# Placa_Final_Embebidos_Hoja2.net
KiCad netlist of a schematic drawn in Altium Designer
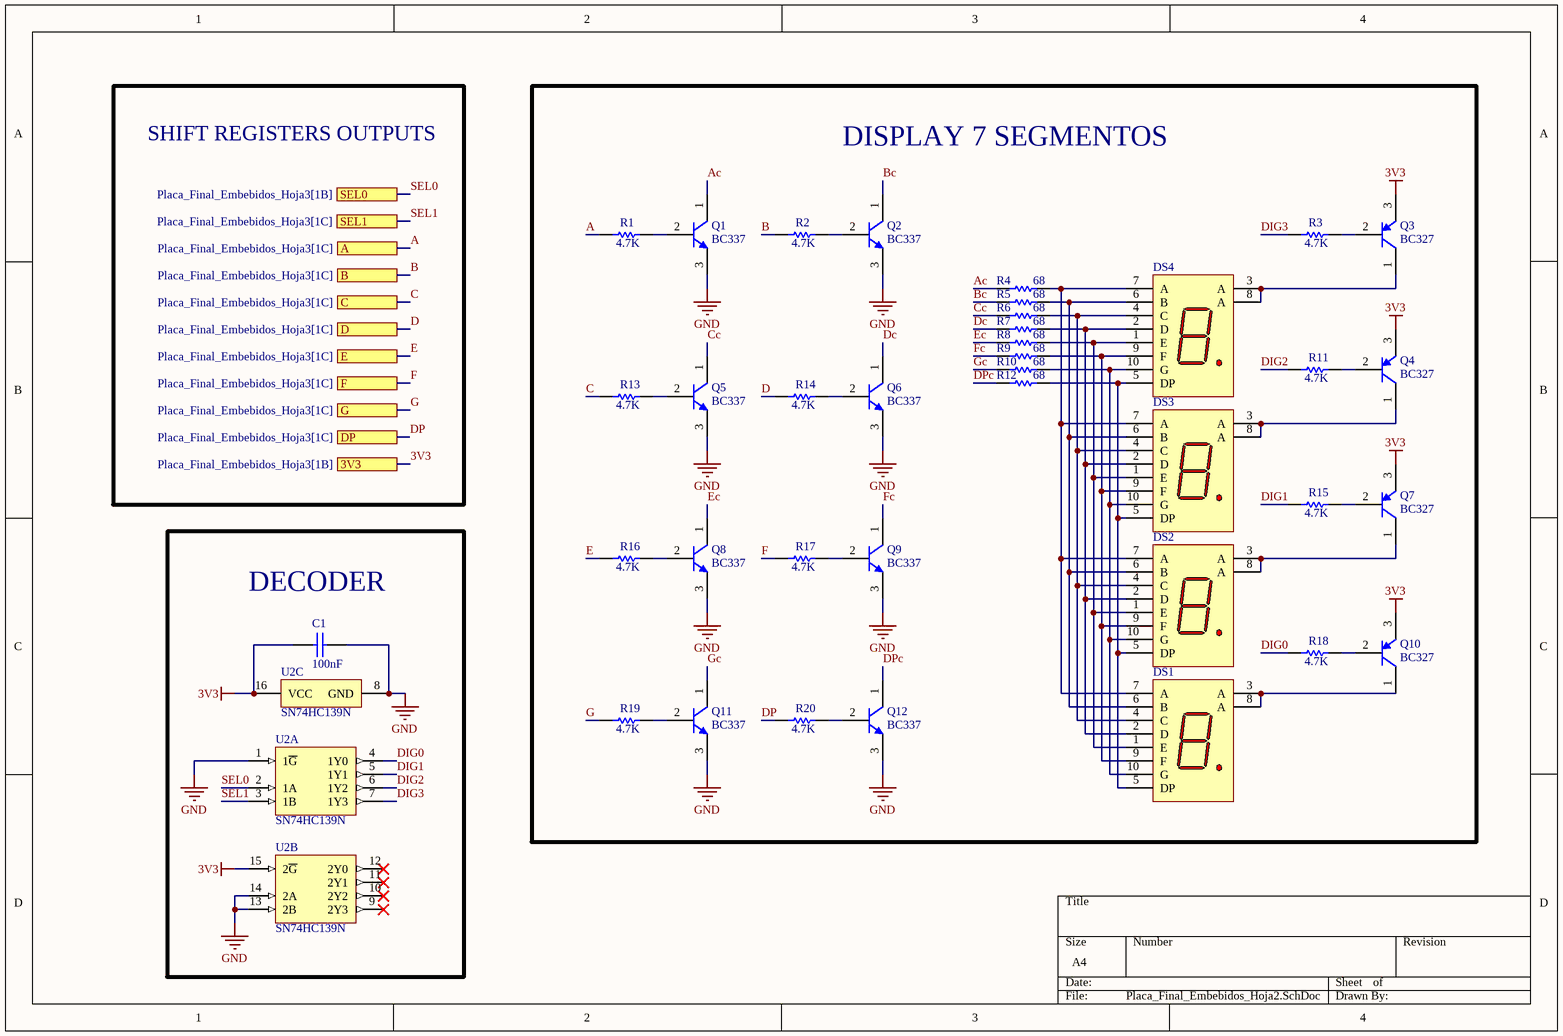
[diagram p0: Placa_Final_Embebidos_Hoja2.SchDoc]

(export (version "E")
  (design (tool "Eeschema 10.0.6"))
  (components
    (comp (ref "C1") (value "100nF") (footprint "CAP200") (libsource (lib "LIB PIO IX") (part "CAP")))
    (comp (ref "DS1")
      (value "~")
      (footprint "WL-T7DS_L17.5W12.4H7")
      (description "7-Seg Display, Comm Anode, Super Red Rohs Compliant: Yes")
      (libsource (lib "Altium Content Vault") (part "7 Segments_Red_CA_type 1"))
    )
    (comp (ref "DS2")
      (value "~")
      (footprint "WL-T7DS_L17.5W12.4H7")
      (description "7-Seg Display, Comm Anode, Super Red Rohs Compliant: Yes")
      (libsource (lib "Altium Content Vault") (part "7 Segments_Red_CA_type 1"))
    )
    (comp (ref "DS3")
      (value "~")
      (footprint "WL-T7DS_L17.5W12.4H7")
      (description "7-Seg Display, Comm Anode, Super Red Rohs Compliant: Yes")
      (libsource (lib "Altium Content Vault") (part "7 Segments_Red_CA_type 1"))
    )
    (comp (ref "DS4")
      (value "~")
      (footprint "WL-T7DS_L17.5W12.4H7")
      (description "7-Seg Display, Comm Anode, Super Red Rohs Compliant: Yes")
      (libsource (lib "Altium Content Vault") (part "7 Segments_Red_CA_type 1"))
    )
    (comp (ref "Q1")
      (value "BC337")
      (footprint "ONSC-TO-92-3-29-11_AM_BL")
      (description "Amplifier Transistor, NPN Silicon, 3-Pin TO-92, Pb-Free, Ammo Box")
      (fields (field (name "PARTNUMBER") "BC337-40ZL1G") (field (name "MANUFACTURER") "On Semiconductor"))
      (libsource (lib "Altium Content Vault") (part "ONSC-NPN-C1B2E3-3"))
    )
    (comp (ref "Q2")
      (value "BC337")
      (footprint "ONSC-TO-92-3-29-11_AM_BL")
      (description "Amplifier Transistor, NPN Silicon, 3-Pin TO-92, Pb-Free, Ammo Box")
      (fields (field (name "PARTNUMBER") "BC337-40ZL1G") (field (name "MANUFACTURER") "On Semiconductor"))
      (libsource (lib "Altium Content Vault") (part "ONSC-NPN-C1B2E3-3"))
    )
    (comp (ref "Q3")
      (value "BC327")
      (footprint "ONSC-TO-92-3-29-11_AM_BL")
      (description "Amplifier Transistor, PNP Silicon, 3-Pin TO-92, Pb-Free, Ammo Box")
      (fields (field (name "MANUFACTURER") "On Semiconductor") (field (name "PARTNUMBER") "BC327-25ZL1G"))
      (libsource (lib "Altium Content Vault") (part "ONSC-PNP-C1B2E3-3"))
    )
    (comp (ref "Q4")
      (value "BC327")
      (footprint "ONSC-TO-92-3-29-11_AM_BL")
      (description "Amplifier Transistor, PNP Silicon, 3-Pin TO-92, Pb-Free, Ammo Box")
      (fields (field (name "MANUFACTURER") "On Semiconductor") (field (name "PARTNUMBER") "BC327-25ZL1G"))
      (libsource (lib "Altium Content Vault") (part "ONSC-PNP-C1B2E3-3"))
    )
    (comp (ref "Q5")
      (value "BC337")
      (footprint "ONSC-TO-92-3-29-11_AM_BL")
      (description "Amplifier Transistor, NPN Silicon, 3-Pin TO-92, Pb-Free, Ammo Box")
      (fields (field (name "PARTNUMBER") "BC337-40ZL1G") (field (name "MANUFACTURER") "On Semiconductor"))
      (libsource (lib "Altium Content Vault") (part "ONSC-NPN-C1B2E3-3"))
    )
    (comp (ref "Q6")
      (value "BC337")
      (footprint "ONSC-TO-92-3-29-11_AM_BL")
      (description "Amplifier Transistor, NPN Silicon, 3-Pin TO-92, Pb-Free, Ammo Box")
      (fields (field (name "PARTNUMBER") "BC337-40ZL1G") (field (name "MANUFACTURER") "On Semiconductor"))
      (libsource (lib "Altium Content Vault") (part "ONSC-NPN-C1B2E3-3"))
    )
    (comp (ref "Q7")
      (value "BC327")
      (footprint "ONSC-TO-92-3-29-11_AM_BL")
      (description "Amplifier Transistor, PNP Silicon, 3-Pin TO-92, Pb-Free, Ammo Box")
      (fields (field (name "MANUFACTURER") "On Semiconductor") (field (name "PARTNUMBER") "BC327-25ZL1G"))
      (libsource (lib "Altium Content Vault") (part "ONSC-PNP-C1B2E3-3"))
    )
    (comp (ref "Q8")
      (value "BC337")
      (footprint "ONSC-TO-92-3-29-11_AM_BL")
      (description "Amplifier Transistor, NPN Silicon, 3-Pin TO-92, Pb-Free, Ammo Box")
      (fields (field (name "PARTNUMBER") "BC337-40ZL1G") (field (name "MANUFACTURER") "On Semiconductor"))
      (libsource (lib "Altium Content Vault") (part "ONSC-NPN-C1B2E3-3"))
    )
    (comp (ref "Q9")
      (value "BC337")
      (footprint "ONSC-TO-92-3-29-11_AM_BL")
      (description "Amplifier Transistor, NPN Silicon, 3-Pin TO-92, Pb-Free, Ammo Box")
      (fields (field (name "PARTNUMBER") "BC337-40ZL1G") (field (name "MANUFACTURER") "On Semiconductor"))
      (libsource (lib "Altium Content Vault") (part "ONSC-NPN-C1B2E3-3"))
    )
    (comp (ref "Q10")
      (value "BC327")
      (footprint "ONSC-TO-92-3-29-11_AM_BL")
      (description "Amplifier Transistor, PNP Silicon, 3-Pin TO-92, Pb-Free, Ammo Box")
      (fields (field (name "MANUFACTURER") "On Semiconductor") (field (name "PARTNUMBER") "BC327-25ZL1G"))
      (libsource (lib "Altium Content Vault") (part "ONSC-PNP-C1B2E3-3"))
    )
    (comp (ref "Q11")
      (value "BC337")
      (footprint "ONSC-TO-92-3-29-11_AM_BL")
      (description "Amplifier Transistor, NPN Silicon, 3-Pin TO-92, Pb-Free, Ammo Box")
      (fields (field (name "PARTNUMBER") "BC337-40ZL1G") (field (name "MANUFACTURER") "On Semiconductor"))
      (libsource (lib "Altium Content Vault") (part "ONSC-NPN-C1B2E3-3"))
    )
    (comp (ref "Q12")
      (value "BC337")
      (footprint "ONSC-TO-92-3-29-11_AM_BL")
      (description "Amplifier Transistor, NPN Silicon, 3-Pin TO-92, Pb-Free, Ammo Box")
      (fields (field (name "PARTNUMBER") "BC337-40ZL1G") (field (name "MANUFACTURER") "On Semiconductor"))
      (libsource (lib "Altium Content Vault") (part "ONSC-NPN-C1B2E3-3"))
    )
    (comp (ref "R1") (value "4.7K") (footprint "RES400") (libsource (lib "LIB PIO IX") (part "RES")))
    (comp (ref "R2") (value "4.7K") (footprint "RES400") (libsource (lib "LIB PIO IX") (part "RES")))
    (comp (ref "R3") (value "4.7K") (footprint "RES400") (libsource (lib "LIB PIO IX") (part "RES")))
    (comp (ref "R4") (value "68") (footprint "RES400") (libsource (lib "LIB PIO IX") (part "RES")))
    (comp (ref "R5") (value "68") (footprint "RES400") (libsource (lib "LIB PIO IX") (part "RES")))
    (comp (ref "R6") (value "68") (footprint "RES400") (libsource (lib "LIB PIO IX") (part "RES")))
    (comp (ref "R7") (value "68") (footprint "RES400") (libsource (lib "LIB PIO IX") (part "RES")))
    (comp (ref "R8") (value "68") (footprint "RES400") (libsource (lib "LIB PIO IX") (part "RES")))
    (comp (ref "R9") (value "68") (footprint "RES400") (libsource (lib "LIB PIO IX") (part "RES")))
    (comp (ref "R10") (value "68") (footprint "RES400") (libsource (lib "LIB PIO IX") (part "RES")))
    (comp (ref "R11") (value "4.7K") (footprint "RES400") (libsource (lib "LIB PIO IX") (part "RES")))
    (comp (ref "R12") (value "68") (footprint "RES400") (libsource (lib "LIB PIO IX") (part "RES")))
    (comp (ref "R13") (value "4.7K") (footprint "RES400") (libsource (lib "LIB PIO IX") (part "RES")))
    (comp (ref "R14") (value "4.7K") (footprint "RES400") (libsource (lib "LIB PIO IX") (part "RES")))
    (comp (ref "R15") (value "4.7K") (footprint "RES400") (libsource (lib "LIB PIO IX") (part "RES")))
    (comp (ref "R16") (value "4.7K") (footprint "RES400") (libsource (lib "LIB PIO IX") (part "RES")))
    (comp (ref "R17") (value "4.7K") (footprint "RES400") (libsource (lib "LIB PIO IX") (part "RES")))
    (comp (ref "R18") (value "4.7K") (footprint "RES400") (libsource (lib "LIB PIO IX") (part "RES")))
    (comp (ref "R19") (value "4.7K") (footprint "RES400") (libsource (lib "LIB PIO IX") (part "RES")))
    (comp (ref "R20") (value "4.7K") (footprint "RES400") (libsource (lib "LIB PIO IX") (part "RES")))
    (comp (ref "U2")
      (value "SN74HC139N")
      (footprint "N0016A")
      (description "Dual 2-Line To 4-Line Decoders/Demultiplexers, N0016A, TUBE")
      (fields
        (field (name "GENERIC PART NUMBER") "SN74HC139")
        (field (name "MANUFACTURER") "Texas Instruments")
      )
      (libsource (lib "Altium Content Vault") (part "TI-CD_SNX4XXX139-16"))
    )
  )
  (nets
    (net (code "1") (name "/A") (class "Default")
      (node (ref "R1") (pin "1") (pinfunction "1_1") (pintype "passive"))
    )
    (net (code "2") (name "/Ac") (class "Default")
      (node (ref "Q1") (pin "1") (pinfunction "C_1") (pintype "passive"))
      (node (ref "R4") (pin "1") (pinfunction "1_1") (pintype "passive"))
    )
    (net (code "3") (name "/B") (class "Default")
      (node (ref "R2") (pin "1") (pinfunction "1_1") (pintype "passive"))
    )
    (net (code "4") (name "/Bc") (class "Default")
      (node (ref "Q2") (pin "1") (pinfunction "C_1") (pintype "passive"))
      (node (ref "R5") (pin "1") (pinfunction "1_1") (pintype "passive"))
    )
    (net (code "5") (name "/C") (class "Default")
      (node (ref "R13") (pin "1") (pinfunction "1_1") (pintype "passive"))
    )
    (net (code "6") (name "/Cc") (class "Default")
      (node (ref "Q5") (pin "1") (pinfunction "C_1") (pintype "passive"))
      (node (ref "R6") (pin "1") (pinfunction "1_1") (pintype "passive"))
    )
    (net (code "7") (name "/D") (class "Default")
      (node (ref "R14") (pin "1") (pinfunction "1_1") (pintype "passive"))
    )
    (net (code "8") (name "/DIG0") (class "Default")
      (node (ref "R18") (pin "1") (pinfunction "1_1") (pintype "passive"))
      (node (ref "U2") (pin "4") (pinfunction "1Y0_4") (pintype "output"))
    )
    (net (code "9") (name "/DIG1") (class "Default")
      (node (ref "R15") (pin "1") (pinfunction "1_1") (pintype "passive"))
      (node (ref "U2") (pin "5") (pinfunction "1Y1_5") (pintype "output"))
    )
    (net (code "10") (name "/DIG2") (class "Default")
      (node (ref "R11") (pin "1") (pinfunction "1_1") (pintype "passive"))
      (node (ref "U2") (pin "6") (pinfunction "1Y2_6") (pintype "output"))
    )
    (net (code "11") (name "/DIG3") (class "Default")
      (node (ref "R3") (pin "1") (pinfunction "1_1") (pintype "passive"))
      (node (ref "U2") (pin "7") (pinfunction "1Y3_7") (pintype "output"))
    )
    (net (code "12") (name "/DP") (class "Default")
      (node (ref "R20") (pin "1") (pinfunction "1_1") (pintype "passive"))
    )
    (net (code "13") (name "/DPc") (class "Default")
      (node (ref "Q12") (pin "1") (pinfunction "C_1") (pintype "passive"))
      (node (ref "R12") (pin "1") (pinfunction "1_1") (pintype "passive"))
    )
    (net (code "14") (name "/Dc") (class "Default")
      (node (ref "Q6") (pin "1") (pinfunction "C_1") (pintype "passive"))
      (node (ref "R7") (pin "1") (pinfunction "1_1") (pintype "passive"))
    )
    (net (code "15") (name "/E") (class "Default")
      (node (ref "R16") (pin "1") (pinfunction "1_1") (pintype "passive"))
    )
    (net (code "16") (name "/Ec") (class "Default")
      (node (ref "Q8") (pin "1") (pinfunction "C_1") (pintype "passive"))
      (node (ref "R8") (pin "1") (pinfunction "1_1") (pintype "passive"))
    )
    (net (code "17") (name "/F") (class "Default")
      (node (ref "R17") (pin "1") (pinfunction "1_1") (pintype "passive"))
    )
    (net (code "18") (name "/Fc") (class "Default")
      (node (ref "Q9") (pin "1") (pinfunction "C_1") (pintype "passive"))
      (node (ref "R9") (pin "1") (pinfunction "1_1") (pintype "passive"))
    )
    (net (code "19") (name "/G") (class "Default")
      (node (ref "R19") (pin "1") (pinfunction "1_1") (pintype "passive"))
    )
    (net (code "20") (name "/Gc") (class "Default")
      (node (ref "Q11") (pin "1") (pinfunction "C_1") (pintype "passive"))
      (node (ref "R10") (pin "1") (pinfunction "1_1") (pintype "passive"))
    )
    (net (code "21") (name "/SEL0") (class "Default")
      (node (ref "U2") (pin "2") (pinfunction "1A_2") (pintype "input"))
    )
    (net (code "22") (name "/SEL1") (class "Default")
      (node (ref "U2") (pin "3") (pinfunction "1B_3") (pintype "input"))
    )
    (net (code "23") (name "3V3") (class "Default")
      (node (ref "C1") (pin "1") (pinfunction "1_1") (pintype "passive"))
      (node (ref "Q10") (pin "3") (pinfunction "E_3") (pintype "passive"))
      (node (ref "Q3") (pin "3") (pinfunction "E_3") (pintype "passive"))
      (node (ref "Q4") (pin "3") (pinfunction "E_3") (pintype "passive"))
      (node (ref "Q7") (pin "3") (pinfunction "E_3") (pintype "passive"))
      (node (ref "U2") (pin "15") (pinfunction "2~{G}_15") (pintype "input"))
      (node (ref "U2") (pin "16") (pinfunction "VCC_16") (pintype "power_in"))
    )
    (net (code "24") (name "GND") (class "Default")
      (node (ref "C1") (pin "2") (pinfunction "2_2") (pintype "passive"))
      (node (ref "Q1") (pin "3") (pinfunction "E_3") (pintype "passive"))
      (node (ref "Q11") (pin "3") (pinfunction "E_3") (pintype "passive"))
      (node (ref "Q12") (pin "3") (pinfunction "E_3") (pintype "passive"))
      (node (ref "Q2") (pin "3") (pinfunction "E_3") (pintype "passive"))
      (node (ref "Q5") (pin "3") (pinfunction "E_3") (pintype "passive"))
      (node (ref "Q6") (pin "3") (pinfunction "E_3") (pintype "passive"))
      (node (ref "Q8") (pin "3") (pinfunction "E_3") (pintype "passive"))
      (node (ref "Q9") (pin "3") (pinfunction "E_3") (pintype "passive"))
      (node (ref "U2") (pin "1") (pinfunction "1~{G}_1") (pintype "input"))
      (node (ref "U2") (pin "13") (pinfunction "2B_13") (pintype "input"))
      (node (ref "U2") (pin "14") (pinfunction "2A_14") (pintype "input"))
      (node (ref "U2") (pin "8") (pinfunction "GND_8") (pintype "power_in"))
    )
    (net (code "25") (name "Net-(DS1-A-Pad7)") (class "Default")
      (node (ref "DS1") (pin "7") (pinfunction "A_7") (pintype "passive"))
      (node (ref "DS2") (pin "7") (pinfunction "A_7") (pintype "passive"))
      (node (ref "DS3") (pin "7") (pinfunction "A_7") (pintype "passive"))
      (node (ref "DS4") (pin "7") (pinfunction "A_7") (pintype "passive"))
      (node (ref "R4") (pin "2") (pinfunction "2_2") (pintype "passive"))
    )
    (net (code "26") (name "Net-(DS1-B)") (class "Default")
      (node (ref "DS1") (pin "6") (pinfunction "B_6") (pintype "passive"))
      (node (ref "DS2") (pin "6") (pinfunction "B_6") (pintype "passive"))
      (node (ref "DS3") (pin "6") (pinfunction "B_6") (pintype "passive"))
      (node (ref "DS4") (pin "6") (pinfunction "B_6") (pintype "passive"))
      (node (ref "R5") (pin "2") (pinfunction "2_2") (pintype "passive"))
    )
    (net (code "27") (name "Net-(DS1-C)") (class "Default")
      (node (ref "DS1") (pin "4") (pinfunction "C_4") (pintype "passive"))
      (node (ref "DS2") (pin "4") (pinfunction "C_4") (pintype "passive"))
      (node (ref "DS3") (pin "4") (pinfunction "C_4") (pintype "passive"))
      (node (ref "DS4") (pin "4") (pinfunction "C_4") (pintype "passive"))
      (node (ref "R6") (pin "2") (pinfunction "2_2") (pintype "passive"))
    )
    (net (code "28") (name "Net-(DS1-D)") (class "Default")
      (node (ref "DS1") (pin "2") (pinfunction "D_2") (pintype "passive"))
      (node (ref "DS2") (pin "2") (pinfunction "D_2") (pintype "passive"))
      (node (ref "DS3") (pin "2") (pinfunction "D_2") (pintype "passive"))
      (node (ref "DS4") (pin "2") (pinfunction "D_2") (pintype "passive"))
      (node (ref "R7") (pin "2") (pinfunction "2_2") (pintype "passive"))
    )
    (net (code "29") (name "Net-(DS1-DP)") (class "Default")
      (node (ref "DS1") (pin "5") (pinfunction "DP_5") (pintype "passive"))
      (node (ref "DS2") (pin "5") (pinfunction "DP_5") (pintype "passive"))
      (node (ref "DS3") (pin "5") (pinfunction "DP_5") (pintype "passive"))
      (node (ref "DS4") (pin "5") (pinfunction "DP_5") (pintype "passive"))
      (node (ref "R12") (pin "2") (pinfunction "2_2") (pintype "passive"))
    )
    (net (code "30") (name "Net-(DS1-E)") (class "Default")
      (node (ref "DS1") (pin "1") (pinfunction "E_1") (pintype "passive"))
      (node (ref "DS2") (pin "1") (pinfunction "E_1") (pintype "passive"))
      (node (ref "DS3") (pin "1") (pinfunction "E_1") (pintype "passive"))
      (node (ref "DS4") (pin "1") (pinfunction "E_1") (pintype "passive"))
      (node (ref "R8") (pin "2") (pinfunction "2_2") (pintype "passive"))
    )
    (net (code "31") (name "Net-(DS1-F)") (class "Default")
      (node (ref "DS1") (pin "9") (pinfunction "F_9") (pintype "passive"))
      (node (ref "DS2") (pin "9") (pinfunction "F_9") (pintype "passive"))
      (node (ref "DS3") (pin "9") (pinfunction "F_9") (pintype "passive"))
      (node (ref "DS4") (pin "9") (pinfunction "F_9") (pintype "passive"))
      (node (ref "R9") (pin "2") (pinfunction "2_2") (pintype "passive"))
    )
    (net (code "32") (name "Net-(DS1-G)") (class "Default")
      (node (ref "DS1") (pin "10") (pinfunction "G_10") (pintype "passive"))
      (node (ref "DS2") (pin "10") (pinfunction "G_10") (pintype "passive"))
      (node (ref "DS3") (pin "10") (pinfunction "G_10") (pintype "passive"))
      (node (ref "DS4") (pin "10") (pinfunction "G_10") (pintype "passive"))
      (node (ref "R10") (pin "2") (pinfunction "2_2") (pintype "passive"))
    )
    (net (code "33") (name "Net-(Q1-B)") (class "Default")
      (node (ref "Q1") (pin "2") (pinfunction "B_2") (pintype "passive"))
      (node (ref "R1") (pin "2") (pinfunction "2_2") (pintype "passive"))
    )
    (net (code "34") (name "Net-(Q2-B)") (class "Default")
      (node (ref "Q2") (pin "2") (pinfunction "B_2") (pintype "passive"))
      (node (ref "R2") (pin "2") (pinfunction "2_2") (pintype "passive"))
    )
    (net (code "35") (name "Net-(Q3-B)") (class "Default")
      (node (ref "Q3") (pin "2") (pinfunction "B_2") (pintype "passive"))
      (node (ref "R3") (pin "2") (pinfunction "2_2") (pintype "passive"))
    )
    (net (code "36") (name "Net-(Q3-C)") (class "Default")
      (node (ref "DS4") (pin "3") (pinfunction "A_3") (pintype "passive"))
      (node (ref "DS4") (pin "8") (pinfunction "A_8") (pintype "passive"))
      (node (ref "Q3") (pin "1") (pinfunction "C_1") (pintype "passive"))
    )
    (net (code "37") (name "Net-(Q4-B)") (class "Default")
      (node (ref "Q4") (pin "2") (pinfunction "B_2") (pintype "passive"))
      (node (ref "R11") (pin "2") (pinfunction "2_2") (pintype "passive"))
    )
    (net (code "38") (name "Net-(Q4-C)") (class "Default")
      (node (ref "DS3") (pin "3") (pinfunction "A_3") (pintype "passive"))
      (node (ref "DS3") (pin "8") (pinfunction "A_8") (pintype "passive"))
      (node (ref "Q4") (pin "1") (pinfunction "C_1") (pintype "passive"))
    )
    (net (code "39") (name "Net-(Q5-B)") (class "Default")
      (node (ref "Q5") (pin "2") (pinfunction "B_2") (pintype "passive"))
      (node (ref "R13") (pin "2") (pinfunction "2_2") (pintype "passive"))
    )
    (net (code "40") (name "Net-(Q6-B)") (class "Default")
      (node (ref "Q6") (pin "2") (pinfunction "B_2") (pintype "passive"))
      (node (ref "R14") (pin "2") (pinfunction "2_2") (pintype "passive"))
    )
    (net (code "41") (name "Net-(Q7-B)") (class "Default")
      (node (ref "Q7") (pin "2") (pinfunction "B_2") (pintype "passive"))
      (node (ref "R15") (pin "2") (pinfunction "2_2") (pintype "passive"))
    )
    (net (code "42") (name "Net-(Q7-C)") (class "Default")
      (node (ref "DS2") (pin "3") (pinfunction "A_3") (pintype "passive"))
      (node (ref "DS2") (pin "8") (pinfunction "A_8") (pintype "passive"))
      (node (ref "Q7") (pin "1") (pinfunction "C_1") (pintype "passive"))
    )
    (net (code "43") (name "Net-(Q8-B)") (class "Default")
      (node (ref "Q8") (pin "2") (pinfunction "B_2") (pintype "passive"))
      (node (ref "R16") (pin "2") (pinfunction "2_2") (pintype "passive"))
    )
    (net (code "44") (name "Net-(Q9-B)") (class "Default")
      (node (ref "Q9") (pin "2") (pinfunction "B_2") (pintype "passive"))
      (node (ref "R17") (pin "2") (pinfunction "2_2") (pintype "passive"))
    )
    (net (code "45") (name "Net-(Q10-B)") (class "Default")
      (node (ref "Q10") (pin "2") (pinfunction "B_2") (pintype "passive"))
      (node (ref "R18") (pin "2") (pinfunction "2_2") (pintype "passive"))
    )
    (net (code "46") (name "Net-(Q10-C)") (class "Default")
      (node (ref "DS1") (pin "3") (pinfunction "A_3") (pintype "passive"))
      (node (ref "DS1") (pin "8") (pinfunction "A_8") (pintype "passive"))
      (node (ref "Q10") (pin "1") (pinfunction "C_1") (pintype "passive"))
    )
    (net (code "47") (name "Net-(Q11-B)") (class "Default")
      (node (ref "Q11") (pin "2") (pinfunction "B_2") (pintype "passive"))
      (node (ref "R19") (pin "2") (pinfunction "2_2") (pintype "passive"))
    )
    (net (code "48") (name "Net-(Q12-B)") (class "Default")
      (node (ref "Q12") (pin "2") (pinfunction "B_2") (pintype "passive"))
      (node (ref "R20") (pin "2") (pinfunction "2_2") (pintype "passive"))
    )
    (net (code "49") (name "unconnected-(U2B-2Y0-Pad12)") (class "Default")
      (node (ref "U2") (pin "12") (pinfunction "2Y0_12") (pintype "output+no_connect"))
    )
    (net (code "50") (name "unconnected-(U2B-2Y1-Pad11)") (class "Default")
      (node (ref "U2") (pin "11") (pinfunction "2Y1_11") (pintype "output+no_connect"))
    )
    (net (code "51") (name "unconnected-(U2B-2Y2-Pad10)") (class "Default")
      (node (ref "U2") (pin "10") (pinfunction "2Y2_10") (pintype "output+no_connect"))
    )
    (net (code "52") (name "unconnected-(U2B-2Y3-Pad9)") (class "Default")
      (node (ref "U2") (pin "9") (pinfunction "2Y3_9") (pintype "output+no_connect"))
    )
  )
)
